# Dualpower_Supply.net
KiCad netlist of a schematic drawn in EAGLE
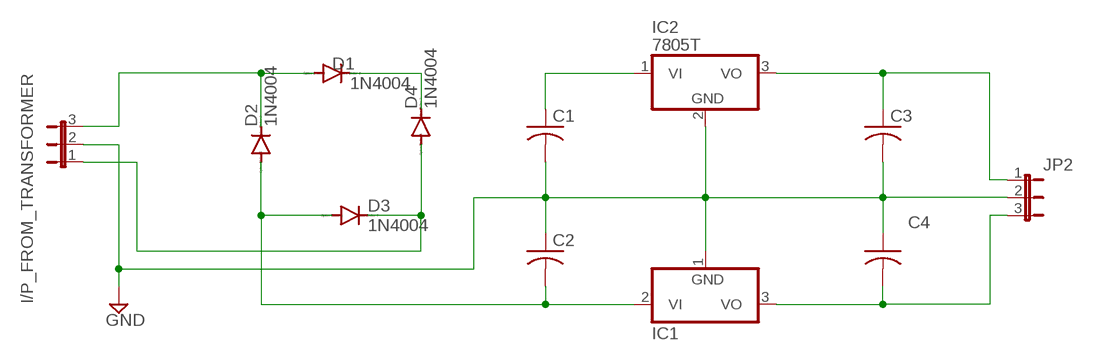
[diagram p0: schematic, sheet 1]

(export (version "E")
  (design (tool "Eeschema 10.0.6"))
  (components
    (comp (ref "C1")
      (value "C-US025-024X044")
      (footprint "eagle-import:C025-024X044")
      (libsource (lib "eagle-import") (part "C-US025-024X044"))
    )
    (comp (ref "C2")
      (value "C-US025-024X044")
      (footprint "eagle-import:C025-024X044")
      (libsource (lib "eagle-import") (part "C-US025-024X044"))
    )
    (comp (ref "C3")
      (value "C-US025-024X044")
      (footprint "eagle-import:C025-024X044")
      (libsource (lib "eagle-import") (part "C-US025-024X044"))
    )
    (comp (ref "C4")
      (value "C-US025-024X044")
      (footprint "eagle-import:C025-024X044")
      (libsource (lib "eagle-import") (part "C-US025-024X044"))
    )
    (comp (ref "D1")
      (value "1N4004")
      (footprint "eagle-import:DO41-10")
      (libsource (lib "eagle-import") (part "1N4004"))
    )
    (comp (ref "D2")
      (value "1N4004")
      (footprint "eagle-import:DO41-10")
      (libsource (lib "eagle-import") (part "1N4004"))
    )
    (comp (ref "D3")
      (value "1N4004")
      (footprint "eagle-import:DO41-10")
      (libsource (lib "eagle-import") (part "1N4004"))
    )
    (comp (ref "D4")
      (value "1N4004")
      (footprint "eagle-import:DO41-10")
      (libsource (lib "eagle-import") (part "1N4004"))
    )
    (comp (ref "I/P_FROM_TRANSFORMER")
      (value "JP2E")
      (footprint "eagle-import:JP2")
      (libsource (lib "eagle-import") (part "JP2E"))
    )
    (comp (ref "IC1")
      (value "7905T")
      (footprint "eagle-import:TO220H")
      (libsource (lib "eagle-import") (part "79T05"))
    )
    (comp (ref "IC2")
      (value "7805T")
      (footprint "eagle-import:TO220H")
      (libsource (lib "eagle-import") (part "78T05"))
    )
    (comp (ref "JP2")
      (value "JP2E")
      (footprint "eagle-import:JP2")
      (libsource (lib "eagle-import") (part "JP2E"))
    )
  )
  (nets
    (net (code "1") (name "GND") (class "Default")
      (node (ref "C1") (pin "2") (pinfunction "2_2") (pintype "passive"))
      (node (ref "C2") (pin "1") (pinfunction "1_1") (pintype "passive"))
      (node (ref "C3") (pin "2") (pinfunction "2_2") (pintype "passive"))
      (node (ref "C4") (pin "1") (pinfunction "1_1") (pintype "passive"))
      (node (ref "I/P_FROM_TRANSFORMER") (pin "2") (pinfunction "2_2") (pintype "passive"))
      (node (ref "IC1") (pin "1") (pinfunction "GND_1") (pintype "passive"))
      (node (ref "IC2") (pin "2") (pinfunction "GND_2") (pintype "passive"))
      (node (ref "JP2") (pin "2") (pinfunction "2_2") (pintype "passive"))
    )
    (net (code "2") (name "Net-(D1-PadA)") (class "Default")
      (node (ref "D1") (pin "A") (pinfunction "A_A") (pintype "passive"))
      (node (ref "D2") (pin "C") (pinfunction "C_C") (pintype "passive"))
      (node (ref "I/P_FROM_TRANSFORMER") (pin "3") (pinfunction "3_3") (pintype "passive"))
    )
    (net (code "3") (name "Net-(D1-PadC)") (class "Default")
      (node (ref "D1") (pin "C") (pinfunction "C_C") (pintype "passive"))
      (node (ref "D4") (pin "C") (pinfunction "C_C") (pintype "passive"))
    )
    (net (code "4") (name "Net-(D3-PadC)") (class "Default")
      (node (ref "D3") (pin "C") (pinfunction "C_C") (pintype "passive"))
      (node (ref "D4") (pin "A") (pinfunction "A_A") (pintype "passive"))
      (node (ref "I/P_FROM_TRANSFORMER") (pin "1") (pinfunction "1_1") (pintype "passive"))
    )
    (net (code "5") (name "Net-(IC1-VI)") (class "Default")
      (node (ref "C2") (pin "2") (pinfunction "2_2") (pintype "passive"))
      (node (ref "D2") (pin "A") (pinfunction "A_A") (pintype "passive"))
      (node (ref "D3") (pin "A") (pinfunction "A_A") (pintype "passive"))
      (node (ref "IC1") (pin "2") (pinfunction "VI_2") (pintype "input"))
    )
    (net (code "6") (name "Net-(IC1-VO)") (class "Default")
      (node (ref "C4") (pin "2") (pinfunction "2_2") (pintype "passive"))
      (node (ref "IC1") (pin "3") (pinfunction "VO_3") (pintype "passive"))
      (node (ref "JP2") (pin "3") (pinfunction "3_3") (pintype "passive"))
    )
    (net (code "7") (name "Net-(IC2-VI)") (class "Default")
      (node (ref "C1") (pin "1") (pinfunction "1_1") (pintype "passive"))
      (node (ref "IC2") (pin "1") (pinfunction "VI_1") (pintype "input"))
    )
    (net (code "8") (name "Net-(IC2-VO)") (class "Default")
      (node (ref "C3") (pin "1") (pinfunction "1_1") (pintype "passive"))
      (node (ref "IC2") (pin "3") (pinfunction "VO_3") (pintype "passive"))
      (node (ref "JP2") (pin "1") (pinfunction "1_1") (pintype "passive"))
    )
  )
)
